# F1C200S.net
KiCad netlist of a schematic drawn in Altium Designer
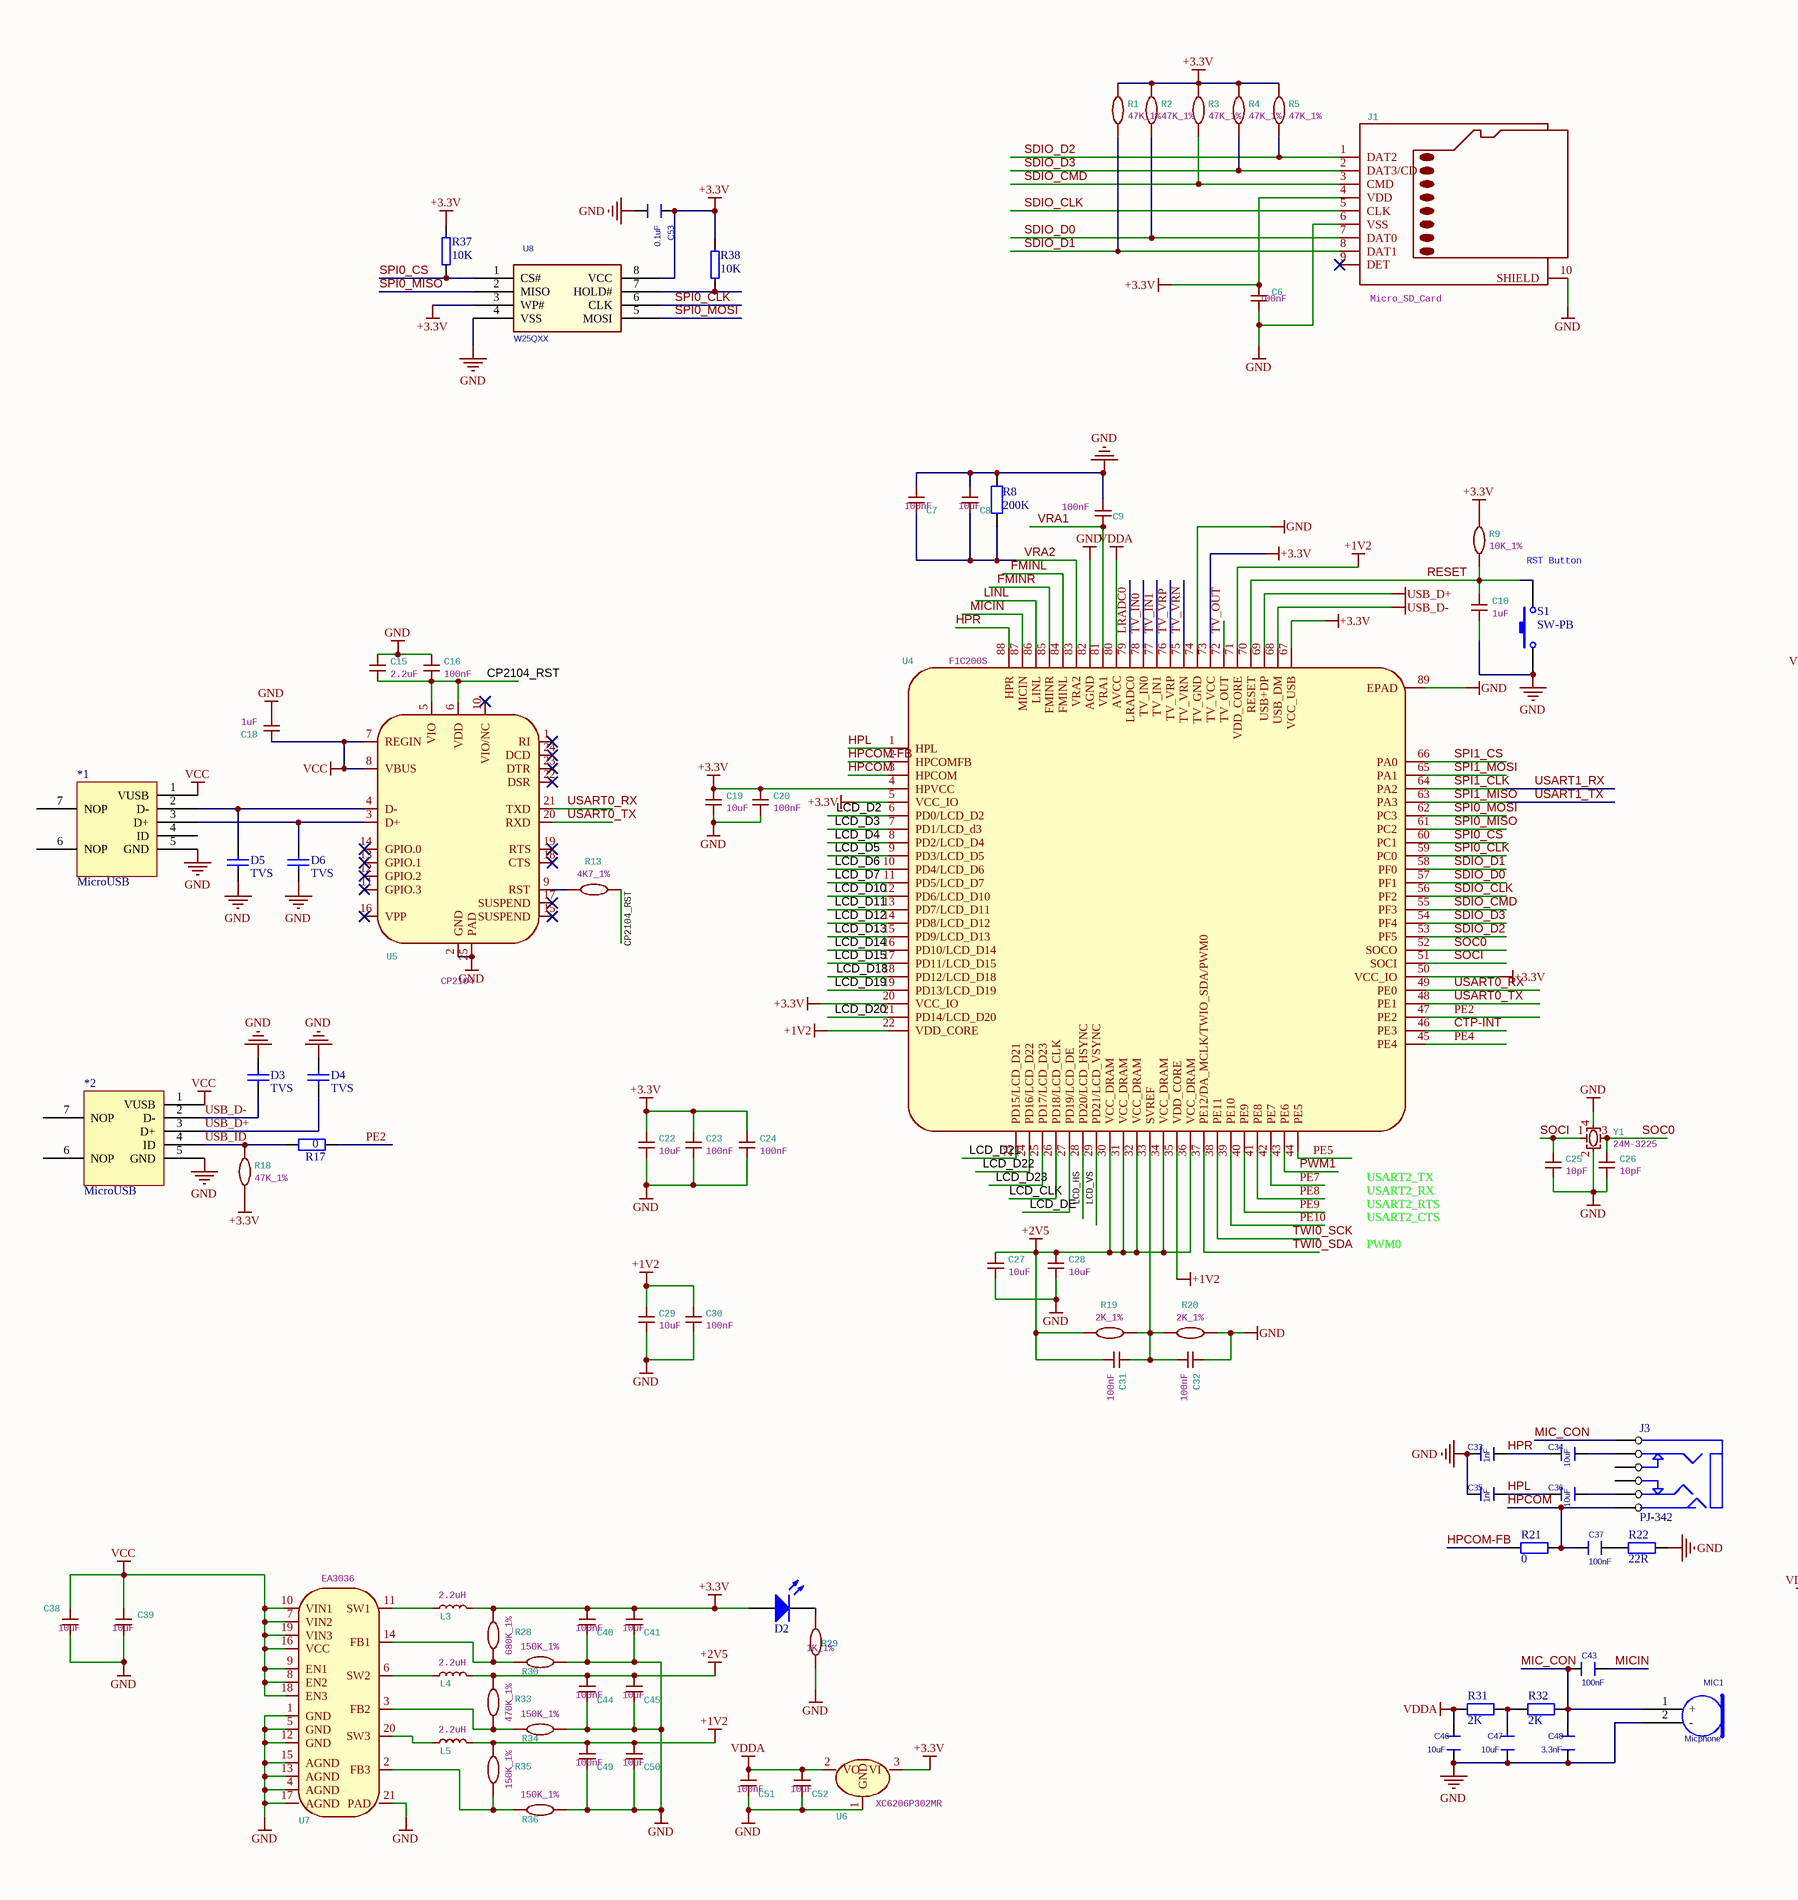
[diagram p0: F1C200S.SchDoc, left]
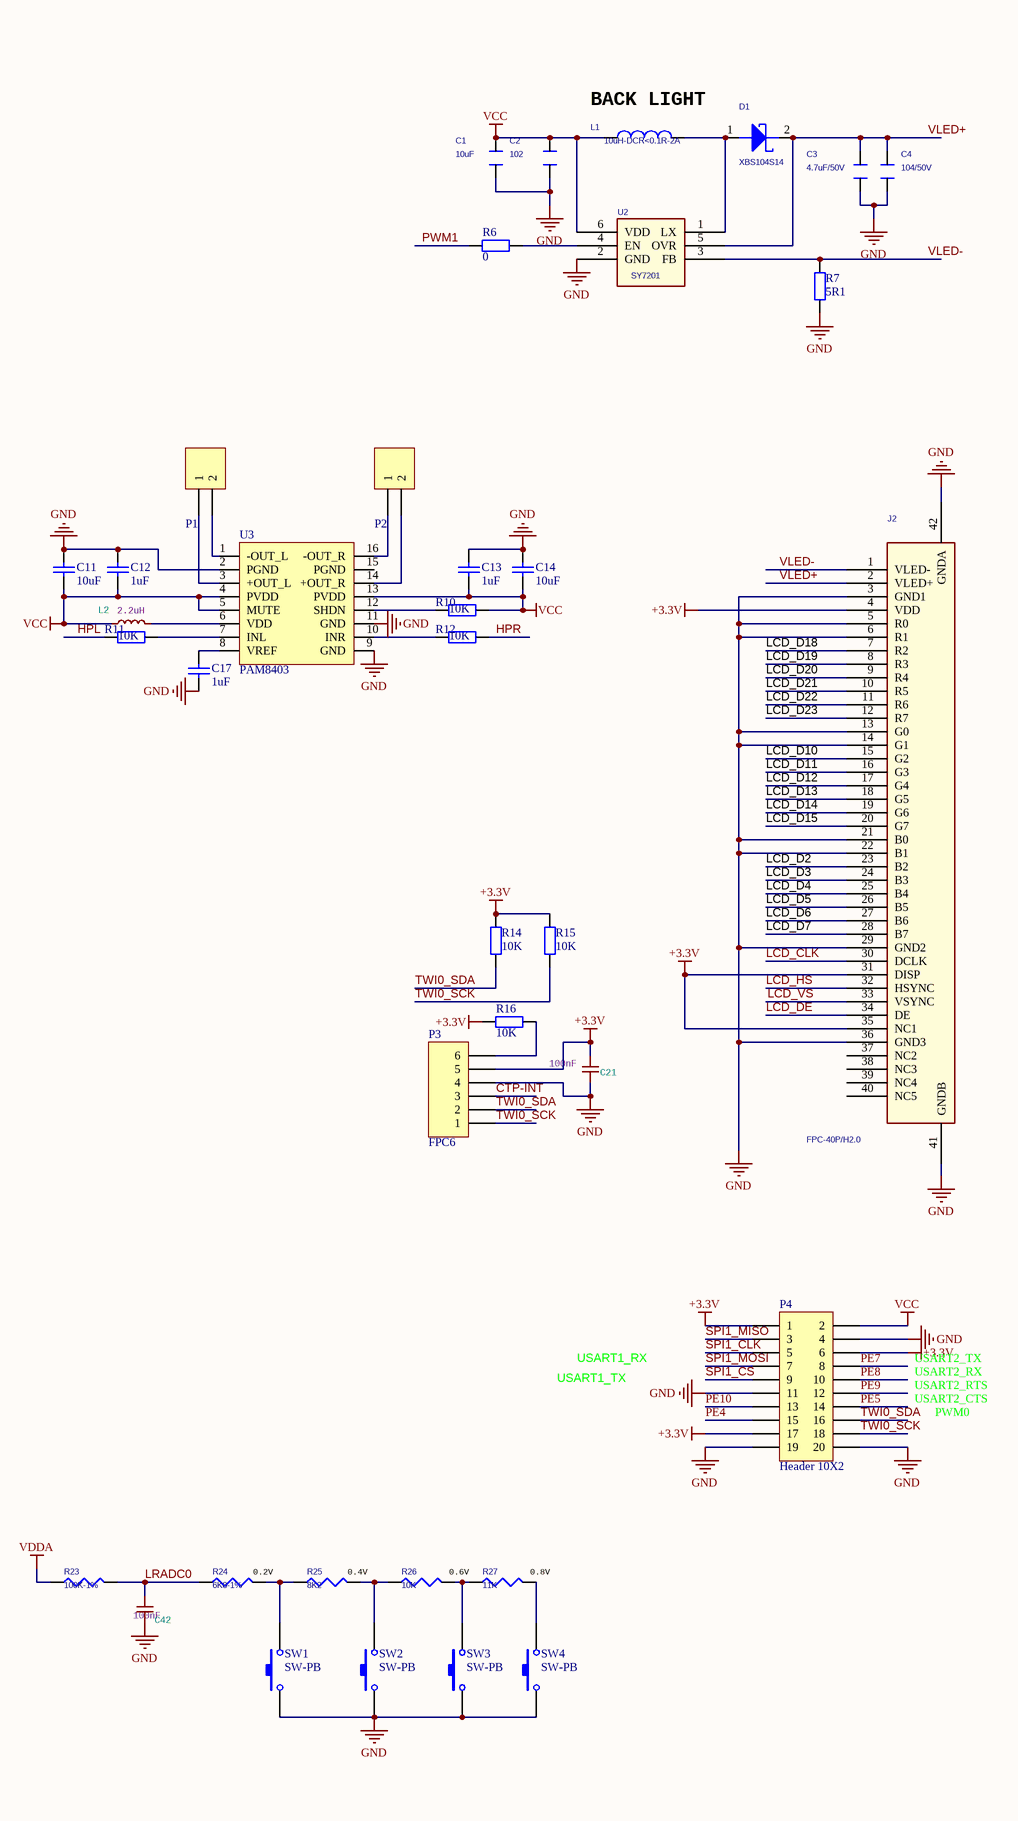
[diagram p1: F1C200S.SchDoc, right]

(export (version "E")
  (design (tool "Eeschema 10.0.6"))
  (components
    (comp (ref "*1")
      (value "MicroUSB")
      (footprint "USB_Micro - 4FP")
      (libsource (lib "USB") (part "MicroUSB"))
    )
    (comp (ref "*2")
      (value "MicroUSB")
      (footprint "USB_Micro - 4FP")
      (libsource (lib "USB") (part "MicroUSB"))
    )
    (comp (ref "C1") (value "10uF") (footprint "C0603") (libsource (lib "*") (part "CAPACITOR_0_Dup5")))
    (comp (ref "C2") (value "102") (footprint "C0603") (libsource (lib "*") (part "CAPACITOR_0_Dup5")))
    (comp (ref "C3") (value "4.7uF/50V") (footprint "C0603") (libsource (lib "*") (part "CAPACITOR_0_Dup5")))
    (comp (ref "C4") (value "104/50V") (footprint "C0603") (libsource (lib "*") (part "CAPACITOR_0_Dup5")))
    (comp (ref "C6")
      (value "03.0009_C0402_100nF")
      (footprint "C0402")
      (libsource (lib "") (part "root_0_03.0009_C0402_100nF__1"))
    )
    (comp (ref "C7")
      (value "03.0009_C0402_100nF")
      (footprint "C0402")
      (libsource (lib "altium-import") (part "root_0_mirrored_03.0009_C0402_100nF_"))
    )
    (comp (ref "C8")
      (value "03.4004_C0603_10uF")
      (footprint "C0603")
      (libsource (lib "altium-import") (part "root_0_mirrored_03.4004_C0603_10uF_"))
    )
    (comp (ref "C9")
      (value "03.0009_C0402_100nF")
      (footprint "C0402")
      (libsource (lib "altium-import") (part "root_3_03.0009_C0402_100nF_"))
    )
    (comp (ref "C10")
      (value "03.0001_C0402_1uF")
      (footprint "C0402")
      (libsource (lib "altium-import") (part "root_0_03.0001_C0402_1uF_"))
    )
    (comp (ref "C11")
      (value "10uF")
      (footprint "C0603")
      (description "无极性电容")
      (fields (field (name "Comment") "Cap") (field (name "PUBLISHER") "Altium Limited"))
      (libsource (lib "fszhang") (part "Cap"))
    )
    (comp (ref "C12")
      (value "1uF")
      (footprint "C0402")
      (description "无极性电容")
      (fields (field (name "Comment") "Cap") (field (name "PUBLISHER") "Altium Limited"))
      (libsource (lib "fszhang") (part "Cap"))
    )
    (comp (ref "C13")
      (value "1uF")
      (footprint "C0402")
      (description "无极性电容")
      (fields (field (name "Comment") "Cap") (field (name "PUBLISHER") "Altium Limited"))
      (libsource (lib "fszhang") (part "Cap"))
    )
    (comp (ref "C14")
      (value "10uF")
      (footprint "C0603")
      (description "无极性电容")
      (fields (field (name "Comment") "Cap") (field (name "PUBLISHER") "Altium Limited"))
      (libsource (lib "fszhang") (part "Cap"))
    )
    (comp (ref "C15")
      (value "03.4002_C0603_2.2uF")
      (footprint "C0402")
      (libsource (lib "altium-import") (part "root_0_03.4002_C0603_2.2uF_"))
    )
    (comp (ref "C16")
      (value "03.0009_C0402_100nF")
      (footprint "C0402")
      (libsource (lib "") (part "root_0_03.0009_C0402_100nF__1"))
    )
    (comp (ref "C17")
      (value "1uF")
      (footprint "C0402")
      (description "无极性电容")
      (fields (field (name "Comment") "Cap") (field (name "PUBLISHER") "Altium Limited"))
      (libsource (lib "fszhang") (part "Cap"))
    )
    (comp (ref "C18")
      (value "03.4001_C0603_1uF")
      (footprint "C0402")
      (libsource (lib "altium-import") (part "root_0_03.4001_C0603_1uF_"))
    )
    (comp (ref "C19")
      (value "03.4004_C0603_10uF")
      (footprint "C0603")
      (libsource (lib "altium-import") (part "root_0_03.4004_C0603_10uF_"))
    )
    (comp (ref "C20")
      (value "03.0009_C0402_100nF")
      (footprint "C0402")
      (libsource (lib "") (part "root_0_03.0009_C0402_100nF__1"))
    )
    (comp (ref "C21")
      (value "03.0009_C0402_100nF")
      (footprint "C0402")
      (libsource (lib "altium-import") (part "root_3_03.0009_C0402_100nF_"))
    )
    (comp (ref "C22")
      (value "03.4004_C0603_10uF")
      (footprint "C0603")
      (libsource (lib "altium-import") (part "root_0_03.4004_C0603_10uF_"))
    )
    (comp (ref "C23")
      (value "03.0009_C0402_100nF")
      (footprint "C0402")
      (libsource (lib "") (part "root_0_03.0009_C0402_100nF__1"))
    )
    (comp (ref "C24")
      (value "03.0009_C0402_100nF")
      (footprint "C0402")
      (libsource (lib "") (part "root_0_03.0009_C0402_100nF__1"))
    )
    (comp (ref "C25")
      (value "03.0003_C0402_10pF")
      (footprint "C0402")
      (libsource (lib "altium-import") (part "root_0_03.0003_C0402_10pF_"))
    )
    (comp (ref "C26")
      (value "03.0003_C0402_10pF")
      (footprint "C0402")
      (libsource (lib "altium-import") (part "root_0_03.0003_C0402_10pF_"))
    )
    (comp (ref "C27")
      (value "03.4004_C0603_10uF")
      (footprint "C0603")
      (libsource (lib "altium-import") (part "root_0_03.4004_C0603_10uF_"))
    )
    (comp (ref "C28")
      (value "03.4004_C0603_10uF")
      (footprint "C0603")
      (libsource (lib "altium-import") (part "root_0_03.4004_C0603_10uF_"))
    )
    (comp (ref "C29")
      (value "03.4004_C0603_10uF")
      (footprint "C0603")
      (libsource (lib "altium-import") (part "root_0_03.4004_C0603_10uF_"))
    )
    (comp (ref "C30")
      (value "03.0009_C0402_100nF")
      (footprint "C0402")
      (libsource (lib "") (part "root_0_03.0009_C0402_100nF__1"))
    )
    (comp (ref "C31")
      (value "03.0009_C0402_100nF")
      (footprint "C0402")
      (libsource (lib "altium-import") (part "root_0_03.0009_C0402_100nF_"))
    )
    (comp (ref "C32")
      (value "03.0009_C0402_100nF")
      (footprint "C0402")
      (libsource (lib "altium-import") (part "root_0_03.0009_C0402_100nF_"))
    )
    (comp (ref "C33") (value "1nF") (footprint "C0402") (libsource (lib "*") (part "CAPACITOR_Dup3")))
    (comp (ref "C34") (value "10uF") (footprint "C0603") (libsource (lib "*") (part "CAPACITOR_Dup3")))
    (comp (ref "C35") (value "1nF") (footprint "C0402") (libsource (lib "*") (part "CAPACITOR_Dup3")))
    (comp (ref "C36") (value "10uF") (footprint "C0603") (libsource (lib "*") (part "CAPACITOR_Dup3")))
    (comp (ref "C37") (value "100nF") (footprint "C0402") (libsource (lib "*") (part "CAPACITOR_Dup3")))
    (comp (ref "C38")
      (value "03.4004_C0603_10uF")
      (footprint "C0603")
      (libsource (lib "altium-import") (part "root_0_mirrored_03.4004_C0603_10uF_"))
    )
    (comp (ref "C39")
      (value "03.4004_C0603_10uF")
      (footprint "C0603")
      (libsource (lib "altium-import") (part "root_0_mirrored_03.4004_C0603_10uF_"))
    )
    (comp (ref "C40")
      (value "03.0009_C0402_100nF")
      (footprint "C0402")
      (libsource (lib "altium-import") (part "root_0_mirrored_03.0009_C0402_100nF_"))
    )
    (comp (ref "C41")
      (value "03.4004_C0603_10uF")
      (footprint "C0603")
      (libsource (lib "altium-import") (part "root_0_mirrored_03.4004_C0603_10uF_"))
    )
    (comp (ref "C42")
      (value "03.0009_C0402_100nF")
      (footprint "C0402")
      (libsource (lib "altium-import") (part "root_0_mirrored_03.0009_C0402_100nF_"))
    )
    (comp (ref "C43") (value "100nF") (footprint "C0402") (libsource (lib "*") (part "CAPACITOR_Dup3")))
    (comp (ref "C44")
      (value "03.0009_C0402_100nF")
      (footprint "C0402")
      (libsource (lib "altium-import") (part "root_0_mirrored_03.0009_C0402_100nF_"))
    )
    (comp (ref "C45")
      (value "03.4004_C0603_10uF")
      (footprint "C0603")
      (libsource (lib "altium-import") (part "root_0_mirrored_03.4004_C0603_10uF_"))
    )
    (comp (ref "C46") (value "10uF") (footprint "C0603") (libsource (lib "*") (part "CAPACITOR_Dup3")))
    (comp (ref "C47") (value "10uF") (footprint "C0603") (libsource (lib "*") (part "CAPACITOR_Dup3")))
    (comp (ref "C48") (value "3.3nF") (footprint "C0402") (libsource (lib "*") (part "CAPACITOR_Dup3")))
    (comp (ref "C49")
      (value "03.0009_C0402_100nF")
      (footprint "C0402")
      (libsource (lib "altium-import") (part "root_0_mirrored_03.0009_C0402_100nF_"))
    )
    (comp (ref "C50")
      (value "03.4004_C0603_10uF")
      (footprint "C0603")
      (libsource (lib "altium-import") (part "root_0_mirrored_03.4004_C0603_10uF_"))
    )
    (comp (ref "C51")
      (value "03.0009_C0402_100nF")
      (footprint "C0402")
      (libsource (lib "altium-import") (part "root_0_mirrored_03.0009_C0402_100nF_"))
    )
    (comp (ref "C52")
      (value "03.4004_C0603_10uF")
      (footprint "C0603")
      (libsource (lib "altium-import") (part "root_0_mirrored_03.4004_C0603_10uF_"))
    )
    (comp (ref "C53") (value "0.1uF") (footprint "C0402") (libsource (lib "*") (part "CAPACITOR_Dup1")))
    (comp (ref "D1")
      (value "XBS104S14")
      (footprint "SOD123")
      (description "RoHS 1.0 Ampere Schottky Barrier Rectifiers  SOD-123")
      (libsource (lib "*") (part "DIODE SCHOTTKY_0"))
    )
    (comp (ref "D2")
      (value "LED0")
      (footprint "0603LED")
      (description "发光二极管")
      (fields (field (name "PUBLISHER") "Altium Limited"))
      (libsource (lib "fszhang") (part "LED0"))
    )
    (comp (ref "D3")
      (value "TVS")
      (footprint "C0402")
      (description "无极性电容")
      (fields (field (name "Comment") "Cap") (field (name "PUBLISHER") "Altium Limited"))
      (libsource (lib "fszhang") (part "Cap"))
    )
    (comp (ref "D4")
      (value "TVS")
      (footprint "C0402")
      (description "无极性电容")
      (fields (field (name "Comment") "Cap") (field (name "PUBLISHER") "Altium Limited"))
      (libsource (lib "fszhang") (part "Cap"))
    )
    (comp (ref "D5")
      (value "TVS")
      (footprint "C0402")
      (description "无极性电容")
      (fields (field (name "Comment") "Cap") (field (name "PUBLISHER") "Altium Limited"))
      (libsource (lib "fszhang") (part "Cap"))
    )
    (comp (ref "D6")
      (value "TVS")
      (footprint "C0402")
      (description "无极性电容")
      (fields (field (name "Comment") "Cap") (field (name "PUBLISHER") "Altium Limited"))
      (libsource (lib "fszhang") (part "Cap"))
    )
    (comp (ref "J1")
      (value "10.0001_Micro_SD_Card")
      (footprint "SDCARD-M")
      (libsource (lib "altium-import") (part "root_0_10.0001_Micro_SD_Card_"))
    )
    (comp (ref "J2")
      (value "FPC-40P/H2.0")
      (footprint "FPC0.5-40P-B")
      (libsource (lib "*") (part "LCD-LW500AC9001_0"))
    )
    (comp (ref "J3") (value "PJ-342") (footprint "PJ-342") (libsource (lib "lpi-nano-dock") (part "PJ-342")))
    (comp (ref "L1")
      (value "10uH-DCR<0.1R-2A")
      (footprint "3015")
      (description "RoHS Power Inductor 22uH 300mA H<1.8MM,CD32")
      (libsource (lib "*") (part "INDUCTOR_3"))
    )
    (comp (ref "L2")
      (value "06.0102_L2520_2.2uH")
      (footprint "3015")
      (libsource (lib "altium-import") (part "root_0_mirrored_06.0102_L2520_2.2uH_"))
    )
    (comp (ref "L3")
      (value "06.0102_L2520_2.2uH")
      (footprint "3015")
      (libsource (lib "altium-import") (part "root_0_mirrored_06.0102_L2520_2.2uH_"))
    )
    (comp (ref "L4")
      (value "06.0102_L2520_2.2uH")
      (footprint "3015")
      (libsource (lib "altium-import") (part "root_0_mirrored_06.0102_L2520_2.2uH_"))
    )
    (comp (ref "L5")
      (value "06.0102_L2520_2.2uH")
      (footprint "3015")
      (libsource (lib "altium-import") (part "root_0_mirrored_06.0102_L2520_2.2uH_"))
    )
    (comp (ref "MIC1") (value "Micphone") (footprint "MIC_6022") (libsource (lib "*") (part "Micphone_0")))
    (comp (ref "P1")
      (value "Header 2")
      (footprint "HDR2X1_A")
      (description "接插件")
      (fields (field (name "PUBLISHER") "Altium Limited"))
      (libsource (lib "fszhang") (part "Header 2"))
    )
    (comp (ref "P2")
      (value "Header 2")
      (footprint "HDR2X1_A")
      (description "接插件")
      (fields (field (name "PUBLISHER") "Altium Limited"))
      (libsource (lib "fszhang") (part "Header 2"))
    )
    (comp (ref "P3")
      (value "FPC6")
      (footprint "FPC0.5-6P-A")
      (description "接插件")
      (fields (field (name "PUBLISHER") "Altium Limited"))
      (libsource (lib "fszhang") (part "Header 6"))
    )
    (comp (ref "P4")
      (value "Header 10X2")
      (footprint "HDR2X10")
      (description "Header, 10-Pin, Dual row")
      (fields (field (name "PUBLISHER") "Altium Limited"))
      (libsource (lib "Miscellaneous Connectors") (part "Header 10X2"))
    )
    (comp (ref "R1")
      (value "02.0014_R0402_10K_1%")
      (footprint "R0402")
      (libsource (lib "altium-import") (part "root_0_02.0014_R0402_47K_1%_"))
    )
    (comp (ref "R2")
      (value "02.0014_R0402_10K_1%")
      (footprint "R0402")
      (libsource (lib "altium-import") (part "root_0_02.0014_R0402_47K_1%_"))
    )
    (comp (ref "R3")
      (value "02.0014_R0402_10K_1%")
      (footprint "R0402")
      (libsource (lib "altium-import") (part "root_0_02.0014_R0402_47K_1%_"))
    )
    (comp (ref "R4")
      (value "02.0014_R0402_10K_1%")
      (footprint "R0402")
      (libsource (lib "altium-import") (part "root_0_02.0014_R0402_47K_1%_"))
    )
    (comp (ref "R5")
      (value "02.0014_R0402_10K_1%")
      (footprint "R0402")
      (libsource (lib "altium-import") (part "root_0_02.0014_R0402_47K_1%_"))
    )
    (comp (ref "R6")
      (value "0")
      (footprint "R0402")
      (description "贴片电阻")
      (fields (field (name "Comment") "Res1") (field (name "PUBLISHER") "Altium Limited"))
      (libsource (lib "") (part "Res1_1"))
    )
    (comp (ref "R7")
      (value "5R1")
      (footprint "R0603")
      (description "贴片电阻")
      (fields (field (name "Comment") "Res1") (field (name "PUBLISHER") "Altium Limited"))
      (libsource (lib "fszhang") (part "Res1"))
    )
    (comp (ref "R8")
      (value "200K")
      (footprint "R0402")
      (description "贴片电阻")
      (fields (field (name "Comment") "Res1") (field (name "PUBLISHER") "Altium Limited"))
      (libsource (lib "") (part "Res1_2"))
    )
    (comp (ref "R9")
      (value "02.0008_R0402_10K_1%")
      (footprint "R0402")
      (libsource (lib "altium-import") (part "root_0_02.0008_R0402_10K_1%_"))
    )
    (comp (ref "R10")
      (value "10K")
      (footprint "R0402")
      (description "贴片电阻")
      (fields (field (name "Comment") "Res1") (field (name "PUBLISHER") "Altium Limited"))
      (libsource (lib "") (part "Res1_2"))
    )
    (comp (ref "R11")
      (value "10K")
      (footprint "R0402")
      (description "贴片电阻")
      (fields (field (name "Comment") "Res1") (field (name "PUBLISHER") "Altium Limited"))
      (libsource (lib "") (part "Res1_3"))
    )
    (comp (ref "R12")
      (value "10K")
      (footprint "R0402")
      (description "贴片电阻")
      (fields (field (name "Comment") "Res1") (field (name "PUBLISHER") "Altium Limited"))
      (libsource (lib "") (part "Res1_2"))
    )
    (comp (ref "R13")
      (value "02.0005_R0402_4K7_1%")
      (footprint "R0402")
      (libsource (lib "altium-import") (part "root_0_02.0005_R0402_4K7_1%_"))
    )
    (comp (ref "R14")
      (value "10K")
      (footprint "R0402")
      (description "贴片电阻")
      (fields (field (name "Comment") "Res1") (field (name "PUBLISHER") "Altium Limited"))
      (libsource (lib "") (part "Res1_1"))
    )
    (comp (ref "R15")
      (value "10K")
      (footprint "R0402")
      (description "贴片电阻")
      (fields (field (name "Comment") "Res1") (field (name "PUBLISHER") "Altium Limited"))
      (libsource (lib "") (part "Res1_1"))
    )
    (comp (ref "R16")
      (value "10K")
      (footprint "R0402")
      (description "贴片电阻")
      (fields (field (name "Comment") "Res1") (field (name "PUBLISHER") "Altium Limited"))
      (libsource (lib "fszhang") (part "Res1"))
    )
    (comp (ref "R17")
      (value "0")
      (footprint "R0402")
      (description "贴片电阻")
      (fields (field (name "Comment") "Res1") (field (name "PUBLISHER") "Altium Limited"))
      (libsource (lib "") (part "Res1_1"))
    )
    (comp (ref "R18")
      (value "02.0014_R0402_10K_1%")
      (footprint "R0402")
      (libsource (lib "altium-import") (part "root_0_02.0014_R0402_47K_1%_"))
    )
    (comp (ref "R19")
      (value "02.0026_R0402_2K_1%")
      (footprint "R0402")
      (libsource (lib "altium-import") (part "root_0_02.0026_R0402_2K_1%_"))
    )
    (comp (ref "R20")
      (value "02.0026_R0402_2K_1%")
      (footprint "R0402")
      (libsource (lib "altium-import") (part "root_0_02.0026_R0402_2K_1%_"))
    )
    (comp (ref "R21")
      (value "0")
      (footprint "R0402")
      (description "贴片电阻")
      (fields (field (name "Comment") "Res1") (field (name "PUBLISHER") "Altium Limited"))
      (libsource (lib "") (part "Res1_3"))
    )
    (comp (ref "R22")
      (value "22R")
      (footprint "R0603")
      (description "贴片电阻")
      (fields (field (name "Comment") "Res1") (field (name "PUBLISHER") "Altium Limited"))
      (libsource (lib "") (part "Res1_3"))
    )
    (comp (ref "R23") (value "100K-1%") (footprint "R0402") (libsource (lib "*") (part "R1 0805_Dup1")))
    (comp (ref "R24") (value "6K8-1%") (footprint "R0402") (libsource (lib "*") (part "R1 0805_Dup1")))
    (comp (ref "R25") (value "8K2") (footprint "R0402") (libsource (lib "*") (part "R1 0805_Dup1")))
    (comp (ref "R26") (value "10K") (footprint "R0402") (libsource (lib "*") (part "R1 0805_Dup1")))
    (comp (ref "R27") (value "11K") (footprint "R0402") (libsource (lib "*") (part "R1 0805_Dup1")))
    (comp (ref "R28")
      (value "02.0025_R0402_680K_1%")
      (footprint "R0402")
      (libsource (lib "altium-import") (part "root_0_mirrored_02.0025_R0402_680K_1%_"))
    )
    (comp (ref "R29")
      (value "02.0003_R0402_1K_1%")
      (footprint "R0402")
      (libsource (lib "altium-import") (part "root_0_mirrored_02.0003_R0402_1K_1%_"))
    )
    (comp (ref "R30")
      (value "02.0023_R0402_150K_1%")
      (footprint "R0402")
      (libsource (lib "altium-import") (part "root_0_mirrored_02.0023_R0402_150K_1%_"))
    )
    (comp (ref "R31")
      (value "2K")
      (footprint "R0402")
      (description "贴片电阻")
      (fields (field (name "Comment") "Res1") (field (name "PUBLISHER") "Altium Limited"))
      (libsource (lib "") (part "Res1_3"))
    )
    (comp (ref "R32")
      (value "2K")
      (footprint "R0402")
      (description "贴片电阻")
      (fields (field (name "Comment") "Res1") (field (name "PUBLISHER") "Altium Limited"))
      (libsource (lib "") (part "Res1_3"))
    )
    (comp (ref "R33")
      (value "02.0024_R0402_470K_1%")
      (footprint "R0402")
      (libsource (lib "altium-import") (part "root_0_mirrored_02.0024_R0402_470K_1%_"))
    )
    (comp (ref "R34")
      (value "02.0023_R0402_150K_1%")
      (footprint "R0402")
      (libsource (lib "altium-import") (part "root_0_mirrored_02.0023_R0402_150K_1%_"))
    )
    (comp (ref "R35")
      (value "02.0023_R0402_150K_1%")
      (footprint "R0402")
      (libsource (lib "") (part "root_0_mirrored_02.0023_R0402_150K_1%__1"))
    )
    (comp (ref "R36")
      (value "02.0023_R0402_150K_1%")
      (footprint "R0402")
      (libsource (lib "altium-import") (part "root_0_mirrored_02.0023_R0402_150K_1%_"))
    )
    (comp (ref "R37")
      (value "10K")
      (footprint "R0402")
      (description "Resistor")
      (libsource (lib "Renhaibo") (part "电阻Ω"))
    )
    (comp (ref "R38")
      (value "10K")
      (footprint "R0402")
      (description "Resistor")
      (libsource (lib "Renhaibo") (part "电阻Ω"))
    )
    (comp (ref "S1")
      (value "SW-PB")
      (footprint "SW_PB4_3*4*2.5")
      (description "微动开关")
      (fields (field (name "PUBLISHER") "Altium Limited"))
      (libsource (lib "fszhang") (part "SW-PB"))
    )
    (comp (ref "SW1")
      (value "SW-PB")
      (footprint "SW_PB4_3*4*2.5")
      (description "微动开关")
      (fields (field (name "PUBLISHER") "Altium Limited"))
      (libsource (lib "fszhang") (part "SW-PB"))
    )
    (comp (ref "SW2")
      (value "SW-PB")
      (footprint "SW_PB4_3*4*2.5")
      (description "微动开关")
      (fields (field (name "PUBLISHER") "Altium Limited"))
      (libsource (lib "fszhang") (part "SW-PB"))
    )
    (comp (ref "SW3")
      (value "SW-PB")
      (footprint "SW_PB4_3*4*2.5")
      (description "微动开关")
      (fields (field (name "PUBLISHER") "Altium Limited"))
      (libsource (lib "fszhang") (part "SW-PB"))
    )
    (comp (ref "SW4")
      (value "SW-PB")
      (footprint "SW_PB4_3*4*2.5")
      (description "微动开关")
      (fields (field (name "PUBLISHER") "Altium Limited"))
      (libsource (lib "fszhang") (part "SW-PB"))
    )
    (comp (ref "U2") (value "SY7201") (footprint "SOT-23-6") (libsource (lib "*") (part "AP3031")))
    (comp (ref "U3") (value "PAM8403") (footprint "SOP-16") (libsource (lib "STM32 SCH") (part "PAM8403")))
    (comp (ref "U4")
      (value "08.0001_F1C200S")
      (footprint "QFN-88_EP_10X10_PITCH0.4MM")
      (libsource (lib "altium-import") (part "root_0_08.0001_F1C200S_"))
    )
    (comp (ref "U5")
      (value "09.0001_CP2104")
      (footprint "QFN-24-1EP_4X4MM_P0.5MM_EP2.6X2.6MM")
      (libsource (lib "altium-import") (part "root_0_09.0001_CP2104_"))
    )
    (comp (ref "U6")
      (value "09.0103_XC6206")
      (footprint "SOT-23")
      (libsource (lib "altium-import") (part "root_0_mirrored_09.0103_XC6206_"))
    )
    (comp (ref "U7")
      (value "09.0102_EA3036")
      (footprint "QFN-20_EP_3X3_PITCH0.4MM")
      (libsource (lib "altium-import") (part "root_0_mirrored_09.0102_EA3036_"))
    )
    (comp (ref "U8") (value "W25QXX") (footprint "SOP-8M(PAD)") (libsource (lib "*") (part "SPI-NOR-SO8")))
    (comp (ref "Y1")
      (value "07.0403_Crystal_24M_3225")
      (footprint "CRYSTAL-2.5X2.0")
      (libsource (lib "altium-import") (part "root_0_07.0403_Crystal_24M_3225_"))
    )
  )
  (nets
    (net (code "1") (name "+1V2") (class "Default")
      (node (ref "C29") (pin "1") (pintype "passive"))
      (node (ref "C30") (pin "1") (pintype "passive"))
      (node (ref "C49") (pin "1") (pintype "passive"))
      (node (ref "C50") (pin "1") (pintype "passive"))
      (node (ref "L5") (pin "1") (pinfunction "1_1") (pintype "passive"))
      (node (ref "R35") (pin "2") (pinfunction "2_2") (pintype "passive"))
      (node (ref "U4") (pin "22") (pinfunction "VDD_CORE_22") (pintype "passive"))
      (node (ref "U4") (pin "35") (pinfunction "VDD_CORE_35") (pintype "passive"))
      (node (ref "U4") (pin "71") (pinfunction "VDD_CORE_71") (pintype "passive"))
    )
    (net (code "2") (name "+2V5") (class "Default")
      (node (ref "C27") (pin "1") (pintype "passive"))
      (node (ref "C28") (pin "1") (pintype "passive"))
      (node (ref "C31") (pin "2") (pintype "passive"))
      (node (ref "C44") (pin "1") (pintype "passive"))
      (node (ref "C45") (pin "1") (pintype "passive"))
      (node (ref "L4") (pin "1") (pinfunction "1_1") (pintype "passive"))
      (node (ref "R19") (pin "2") (pinfunction "2_2") (pintype "passive"))
      (node (ref "R33") (pin "2") (pinfunction "2_2") (pintype "passive"))
      (node (ref "U4") (pin "30") (pinfunction "VCC_DRAM_30") (pintype "passive"))
      (node (ref "U4") (pin "31") (pinfunction "VCC_DRAM_31") (pintype "passive"))
      (node (ref "U4") (pin "32") (pinfunction "VCC_DRAM_32") (pintype "passive"))
      (node (ref "U4") (pin "34") (pinfunction "VCC_DRAM_34") (pintype "passive"))
      (node (ref "U4") (pin "36") (pinfunction "VCC_DRAM_36") (pintype "passive"))
    )
    (net (code "3") (name "+3.3V") (class "Default")
      (node (ref "C19") (pin "1") (pintype "passive"))
      (node (ref "C20") (pin "1") (pintype "passive"))
      (node (ref "C21") (pin "2") (pintype "passive"))
      (node (ref "C22") (pin "1") (pintype "passive"))
      (node (ref "C23") (pin "1") (pintype "passive"))
      (node (ref "C24") (pin "1") (pintype "passive"))
      (node (ref "C40") (pin "1") (pintype "passive"))
      (node (ref "C41") (pin "1") (pintype "passive"))
      (node (ref "C53") (pin "2") (pinfunction "2_2") (pintype "passive"))
      (node (ref "C6") (pin "1") (pintype "passive"))
      (node (ref "D2") (pin "1") (pinfunction "A_1") (pintype "passive"))
      (node (ref "J1") (pin "4") (pinfunction "VDD_4") (pintype "passive"))
      (node (ref "J2") (pin "31") (pinfunction "DISP_31") (pintype "passive"))
      (node (ref "J2") (pin "35") (pinfunction "NC1_35") (pintype "passive"))
      (node (ref "J2") (pin "4") (pinfunction "VDD_4") (pintype "passive"))
      (node (ref "L3") (pin "1") (pinfunction "1_1") (pintype "passive"))
      (node (ref "P3") (pin "5") (pinfunction "5_5") (pintype "passive"))
      (node (ref "P4") (pin "1") (pinfunction "1_1") (pintype "passive"))
      (node (ref "P4") (pin "17") (pinfunction "17_17") (pintype "passive"))
      (node (ref "P4") (pin "6") (pinfunction "6_6") (pintype "passive"))
      (node (ref "R1") (pin "1") (pinfunction "1_1") (pintype "passive"))
      (node (ref "R14") (pin "2") (pinfunction "2_2") (pintype "passive"))
      (node (ref "R15") (pin "2") (pinfunction "2_2") (pintype "passive"))
      (node (ref "R16") (pin "2") (pinfunction "2_2") (pintype "passive"))
      (node (ref "R18") (pin "2") (pinfunction "2_2") (pintype "passive"))
      (node (ref "R2") (pin "1") (pinfunction "1_1") (pintype "passive"))
      (node (ref "R28") (pin "2") (pinfunction "2_2") (pintype "passive"))
      (node (ref "R3") (pin "1") (pinfunction "1_1") (pintype "passive"))
      (node (ref "R37") (pin "1") (pinfunction "1_1") (pintype "passive"))
      (node (ref "R38") (pin "1") (pinfunction "1_1") (pintype "passive"))
      (node (ref "R4") (pin "1") (pinfunction "1_1") (pintype "passive"))
      (node (ref "R5") (pin "1") (pinfunction "1_1") (pintype "passive"))
      (node (ref "R9") (pin "1") (pinfunction "1_1") (pintype "passive"))
      (node (ref "U4") (pin "20") (pinfunction "VCC_IO_20") (pintype "passive"))
      (node (ref "U4") (pin "4") (pinfunction "HPVCC_4") (pintype "passive"))
      (node (ref "U4") (pin "5") (pinfunction "VCC_IO_5") (pintype "passive"))
      (node (ref "U4") (pin "50") (pinfunction "VCC_IO_50") (pintype "passive"))
      (node (ref "U4") (pin "67") (pinfunction "VCC_USB_67") (pintype "passive"))
      (node (ref "U4") (pin "73") (pinfunction "TV_VCC_73") (pintype "passive"))
      (node (ref "U6") (pin "3") (pinfunction "VI_3") (pintype "passive"))
      (node (ref "U8") (pin "3") (pinfunction "WP#_3") (pintype "passive"))
      (node (ref "U8") (pin "8") (pinfunction "VCC_8") (pintype "passive"))
    )
    (net (code "4") (name "/CP2104_RST") (class "Default")
      (node (ref "C15") (pin "2") (pintype "passive"))
      (node (ref "C16") (pin "2") (pintype "passive"))
      (node (ref "R13") (pin "2") (pinfunction "2_2") (pintype "passive"))
      (node (ref "U5") (pin "5") (pinfunction "VIO_5") (pintype "passive"))
      (node (ref "U5") (pin "6") (pinfunction "VDD_6") (pintype "passive"))
    )
    (net (code "5") (name "/CTP-INT") (class "Default")
      (node (ref "P3") (pin "3") (pinfunction "3_3") (pintype "passive"))
      (node (ref "U4") (pin "46") (pinfunction "PE3_46") (pintype "passive"))
    )
    (net (code "6") (name "/FMINL") (class "Default")
      (node (ref "U4") (pin "84") (pinfunction "FMINL_84") (pintype "passive"))
    )
    (net (code "7") (name "/FMINR") (class "Default")
      (node (ref "U4") (pin "85") (pinfunction "FMINR_85") (pintype "passive"))
    )
    (net (code "8") (name "/HPCOM") (class "Default")
      (node (ref "C37") (pin "2") (pinfunction "2_2") (pintype "passive"))
      (node (ref "J3") (pin "3") (pinfunction "GND_3") (pintype "passive"))
      (node (ref "R21") (pin "1") (pinfunction "1_1") (pintype "passive"))
      (node (ref "U4") (pin "3") (pinfunction "HPCOM_3") (pintype "passive"))
    )
    (net (code "9") (name "/HPCOM-FB") (class "Default")
      (node (ref "R21") (pin "2") (pinfunction "2_2") (pintype "passive"))
      (node (ref "U4") (pin "2") (pinfunction "HPCOMFB_2") (pintype "passive"))
    )
    (net (code "10") (name "/HPL") (class "Default")
      (node (ref "C35") (pin "2") (pinfunction "2_2") (pintype "passive"))
      (node (ref "C36") (pin "1") (pinfunction "1_1") (pintype "passive"))
      (node (ref "R11") (pin "2") (pinfunction "2_2") (pintype "passive"))
      (node (ref "U4") (pin "1") (pinfunction "HPL_1") (pintype "passive"))
    )
    (net (code "11") (name "/HPR") (class "Default")
      (node (ref "C33") (pin "2") (pinfunction "2_2") (pintype "passive"))
      (node (ref "C34") (pin "1") (pinfunction "1_1") (pintype "passive"))
      (node (ref "R12") (pin "2") (pinfunction "2_2") (pintype "passive"))
      (node (ref "U4") (pin "88") (pinfunction "HPR_88") (pintype "passive"))
    )
    (net (code "12") (name "/LCD_CLK") (class "Default")
      (node (ref "J2") (pin "30") (pinfunction "DCLK_30") (pintype "passive"))
      (node (ref "U4") (pin "26") (pinfunction "PD18/LCD_CLK_26") (pintype "passive"))
    )
    (net (code "13") (name "/LCD_D2") (class "Default")
      (node (ref "J2") (pin "23") (pinfunction "B2_23") (pintype "passive"))
      (node (ref "U4") (pin "6") (pinfunction "PD0/LCD_D2_6") (pintype "passive"))
    )
    (net (code "14") (name "/LCD_D3") (class "Default")
      (node (ref "J2") (pin "24") (pinfunction "B3_24") (pintype "passive"))
      (node (ref "U4") (pin "7") (pinfunction "PD1/LCD_d3_7") (pintype "passive"))
    )
    (net (code "15") (name "/LCD_D4") (class "Default")
      (node (ref "J2") (pin "25") (pinfunction "B4_25") (pintype "passive"))
      (node (ref "U4") (pin "8") (pinfunction "PD2/LCD_D4_8") (pintype "passive"))
    )
    (net (code "16") (name "/LCD_D5") (class "Default")
      (node (ref "J2") (pin "26") (pinfunction "B5_26") (pintype "passive"))
      (node (ref "U4") (pin "9") (pinfunction "PD3/LCD_D5_9") (pintype "passive"))
    )
    (net (code "17") (name "/LCD_D6") (class "Default")
      (node (ref "J2") (pin "27") (pinfunction "B6_27") (pintype "passive"))
      (node (ref "U4") (pin "10") (pinfunction "PD4/LCD_D6_10") (pintype "passive"))
    )
    (net (code "18") (name "/LCD_D7") (class "Default")
      (node (ref "J2") (pin "28") (pinfunction "B7_28") (pintype "passive"))
      (node (ref "U4") (pin "11") (pinfunction "PD5/LCD_D7_11") (pintype "passive"))
    )
    (net (code "19") (name "/LCD_D10") (class "Default")
      (node (ref "J2") (pin "15") (pinfunction "G2_15") (pintype "passive"))
      (node (ref "U4") (pin "12") (pinfunction "PD6/LCD_D10_12") (pintype "passive"))
    )
    (net (code "20") (name "/LCD_D11") (class "Default")
      (node (ref "J2") (pin "16") (pinfunction "G3_16") (pintype "passive"))
      (node (ref "U4") (pin "13") (pinfunction "PD7/LCD_D11_13") (pintype "passive"))
    )
    (net (code "21") (name "/LCD_D12") (class "Default")
      (node (ref "J2") (pin "17") (pinfunction "G4_17") (pintype "passive"))
      (node (ref "U4") (pin "14") (pinfunction "PD8/LCD_D12_14") (pintype "passive"))
    )
    (net (code "22") (name "/LCD_D13") (class "Default")
      (node (ref "J2") (pin "18") (pinfunction "G5_18") (pintype "passive"))
      (node (ref "U4") (pin "15") (pinfunction "PD9/LCD_D13_15") (pintype "passive"))
    )
    (net (code "23") (name "/LCD_D14") (class "Default")
      (node (ref "J2") (pin "19") (pinfunction "G6_19") (pintype "passive"))
      (node (ref "U4") (pin "16") (pinfunction "PD10/LCD_D14_16") (pintype "passive"))
    )
    (net (code "24") (name "/LCD_D15") (class "Default")
      (node (ref "J2") (pin "20") (pinfunction "G7_20") (pintype "passive"))
      (node (ref "U4") (pin "17") (pinfunction "PD11/LCD_D15_17") (pintype "passive"))
    )
    (net (code "25") (name "/LCD_D18") (class "Default")
      (node (ref "J2") (pin "7") (pinfunction "R2_7") (pintype "passive"))
      (node (ref "U4") (pin "18") (pinfunction "PD12/LCD_D18_18") (pintype "passive"))
    )
    (net (code "26") (name "/LCD_D19") (class "Default")
      (node (ref "J2") (pin "8") (pinfunction "R3_8") (pintype "passive"))
      (node (ref "U4") (pin "19") (pinfunction "PD13/LCD_D19_19") (pintype "passive"))
    )
    (net (code "27") (name "/LCD_D20") (class "Default")
      (node (ref "J2") (pin "9") (pinfunction "R4_9") (pintype "passive"))
      (node (ref "U4") (pin "21") (pinfunction "PD14/LCD_D20_21") (pintype "passive"))
    )
    (net (code "28") (name "/LCD_D21") (class "Default")
      (node (ref "J2") (pin "10") (pinfunction "R5_10") (pintype "passive"))
      (node (ref "U4") (pin "23") (pinfunction "PD15/LCD_D21_23") (pintype "passive"))
    )
    (net (code "29") (name "/LCD_D22") (class "Default")
      (node (ref "J2") (pin "11") (pinfunction "R6_11") (pintype "passive"))
      (node (ref "U4") (pin "24") (pinfunction "PD16/LCD_D22_24") (pintype "passive"))
    )
    (net (code "30") (name "/LCD_D23") (class "Default")
      (node (ref "J2") (pin "12") (pinfunction "R7_12") (pintype "passive"))
      (node (ref "U4") (pin "25") (pinfunction "PD17/LCD_D23_25") (pintype "passive"))
    )
    (net (code "31") (name "/LCD_DE") (class "Default")
      (node (ref "J2") (pin "34") (pinfunction "DE_34") (pintype "passive"))
      (node (ref "U4") (pin "27") (pinfunction "PD19/LCD_DE_27") (pintype "passive"))
    )
    (net (code "32") (name "/LCD_HS") (class "Default")
      (node (ref "J2") (pin "32") (pinfunction "HSYNC_32") (pintype "passive"))
      (node (ref "U4") (pin "28") (pinfunction "PD20/LCD_HSYNC_28") (pintype "passive"))
    )
    (net (code "33") (name "/LCD_VS") (class "Default")
      (node (ref "J2") (pin "33") (pinfunction "VSYNC_33") (pintype "passive"))
      (node (ref "U4") (pin "29") (pinfunction "PD21/LCD_VSYNC_29") (pintype "passive"))
    )
    (net (code "34") (name "/LINL") (class "Default")
      (node (ref "U4") (pin "86") (pinfunction "LINL_86") (pintype "passive"))
    )
    (net (code "35") (name "/LRADC0") (class "Default")
      (node (ref "C42") (pin "1") (pintype "passive"))
      (node (ref "R23") (pin "2") (pinfunction "2_2") (pintype "passive"))
      (node (ref "R24") (pin "1") (pinfunction "1_1") (pintype "passive"))
      (node (ref "U4") (pin "79") (pinfunction "LRADC0_79") (pintype "passive"))
    )
    (net (code "36") (name "/MICIN") (class "Default")
      (node (ref "C43") (pin "1") (pinfunction "1_1") (pintype "passive"))
      (node (ref "U4") (pin "87") (pinfunction "MICIN_87") (pintype "passive"))
    )
    (net (code "37") (name "/MIC_CON") (class "Default")
      (node (ref "C43") (pin "2") (pinfunction "2_2") (pintype "passive"))
      (node (ref "C48") (pin "1") (pinfunction "1_1") (pintype "passive"))
      (node (ref "J3") (pin "2") (pinfunction "MIC_2") (pintype "passive"))
      (node (ref "MIC1") (pin "1") (pinfunction "+_1") (pintype "passive"))
      (node (ref "R32") (pin "1") (pinfunction "1_1") (pintype "passive"))
    )
    (net (code "38") (name "/PE2") (class "Default")
      (node (ref "R17") (pin "2") (pinfunction "2_2") (pintype "passive"))
      (node (ref "U4") (pin "47") (pinfunction "PE2_47") (pintype "passive"))
    )
    (net (code "39") (name "/PE4") (class "Default")
      (node (ref "P4") (pin "15") (pinfunction "15_15") (pintype "passive"))
      (node (ref "U4") (pin "45") (pinfunction "PE4_45") (pintype "passive"))
    )
    (net (code "40") (name "/PE5") (class "Default")
      (node (ref "P4") (pin "14") (pinfunction "14_14") (pintype "passive"))
      (node (ref "U4") (pin "44") (pinfunction "PE5_44") (pintype "passive"))
    )
    (net (code "41") (name "/PE7") (class "Default")
      (node (ref "P4") (pin "8") (pinfunction "8_8") (pintype "passive"))
      (node (ref "U4") (pin "42") (pinfunction "PE7_42") (pintype "passive"))
    )
    (net (code "42") (name "/PE8") (class "Default")
      (node (ref "P4") (pin "10") (pinfunction "10_10") (pintype "passive"))
      (node (ref "U4") (pin "41") (pinfunction "PE8_41") (pintype "passive"))
    )
    (net (code "43") (name "/PE9") (class "Default")
      (node (ref "P4") (pin "12") (pinfunction "12_12") (pintype "passive"))
      (node (ref "U4") (pin "40") (pinfunction "PE9_40") (pintype "passive"))
    )
    (net (code "44") (name "/PE10") (class "Default")
      (node (ref "P4") (pin "13") (pinfunction "13_13") (pintype "passive"))
      (node (ref "U4") (pin "39") (pinfunction "PE10_39") (pintype "passive"))
    )
    (net (code "46") (name "/PWM1") (class "Default")
      (node (ref "R6") (pin "1") (pinfunction "1_1") (pintype "passive"))
      (node (ref "U4") (pin "43") (pinfunction "PE6_43") (pintype "passive"))
    )
    (net (code "47") (name "/RESET") (class "Default")
      (node (ref "C10") (pin "1") (pintype "passive"))
      (node (ref "R9") (pin "2") (pinfunction "2_2") (pintype "passive"))
      (node (ref "S1") (pin "2") (pinfunction "2_2") (pintype "passive"))
      (node (ref "U4") (pin "70") (pinfunction "RESET_70") (pintype "passive"))
    )
    (net (code "48") (name "/SDIO_CLK") (class "Default")
      (node (ref "J1") (pin "5") (pinfunction "CLK_5") (pintype "passive"))
      (node (ref "U4") (pin "56") (pinfunction "PF2_56") (pintype "passive"))
    )
    (net (code "49") (name "/SDIO_CMD") (class "Default")
      (node (ref "J1") (pin "3") (pinfunction "CMD_3") (pintype "passive"))
      (node (ref "R3") (pin "2") (pinfunction "2_2") (pintype "passive"))
      (node (ref "U4") (pin "55") (pinfunction "PF3_55") (pintype "passive"))
    )
    (net (code "50") (name "/SDIO_D0") (class "Default")
      (node (ref "J1") (pin "7") (pinfunction "DAT0_7") (pintype "passive"))
      (node (ref "R2") (pin "2") (pinfunction "2_2") (pintype "passive"))
      (node (ref "U4") (pin "57") (pinfunction "PF1_57") (pintype "passive"))
    )
    (net (code "51") (name "/SDIO_D1") (class "Default")
      (node (ref "J1") (pin "8") (pinfunction "DAT1_8") (pintype "passive"))
      (node (ref "R1") (pin "2") (pinfunction "2_2") (pintype "passive"))
      (node (ref "U4") (pin "58") (pinfunction "PF0_58") (pintype "passive"))
    )
    (net (code "52") (name "/SDIO_D2") (class "Default")
      (node (ref "J1") (pin "1") (pinfunction "DAT2_1") (pintype "passive"))
      (node (ref "R5") (pin "2") (pinfunction "2_2") (pintype "passive"))
      (node (ref "U4") (pin "53") (pinfunction "PF5_53") (pintype "passive"))
    )
    (net (code "53") (name "/SDIO_D3") (class "Default")
      (node (ref "J1") (pin "2") (pinfunction "DAT3/CD_2") (pintype "passive"))
      (node (ref "R4") (pin "2") (pinfunction "2_2") (pintype "passive"))
      (node (ref "U4") (pin "54") (pinfunction "PF4_54") (pintype "passive"))
    )
    (net (code "54") (name "/SOC0") (class "Default")
      (node (ref "C26") (pin "1") (pintype "passive"))
      (node (ref "U4") (pin "52") (pinfunction "SOCO_52") (pintype "passive"))
      (node (ref "Y1") (pin "3") (pinfunction "3_3") (pintype "passive"))
    )
    (net (code "55") (name "/SOCI") (class "Default")
      (node (ref "C25") (pin "1") (pintype "passive"))
      (node (ref "U4") (pin "51") (pinfunction "SOCI_51") (pintype "passive"))
      (node (ref "Y1") (pin "1") (pinfunction "1_1") (pintype "passive"))
    )
    (net (code "56") (name "/SPI0_CLK") (class "Default")
      (node (ref "U4") (pin "59") (pinfunction "PC0_59") (pintype "passive"))
      (node (ref "U8") (pin "6") (pinfunction "CLK_6") (pintype "passive"))
    )
    (net (code "57") (name "/SPI0_CS") (class "Default")
      (node (ref "R37") (pin "2") (pinfunction "2_2") (pintype "passive"))
      (node (ref "U4") (pin "60") (pinfunction "PC1_60") (pintype "passive"))
      (node (ref "U8") (pin "1") (pinfunction "CS#_1") (pintype "passive"))
    )
    (net (code "58") (name "/SPI0_MISO") (class "Default")
      (node (ref "U4") (pin "61") (pinfunction "PC2_61") (pintype "passive"))
      (node (ref "U8") (pin "2") (pinfunction "MISO_2") (pintype "passive"))
    )
    (net (code "59") (name "/SPI0_MOSI") (class "Default")
      (node (ref "U4") (pin "62") (pinfunction "PC3_62") (pintype "passive"))
      (node (ref "U8") (pin "5") (pinfunction "MOSI_5") (pintype "passive"))
    )
    (net (code "60") (name "/SPI1_CLK") (class "Default")
      (node (ref "P4") (pin "5") (pinfunction "5_5") (pintype "passive"))
      (node (ref "U4") (pin "64") (pinfunction "PA2_64") (pintype "passive"))
    )
    (net (code "61") (name "/SPI1_CS") (class "Default")
      (node (ref "P4") (pin "9") (pinfunction "9_9") (pintype "passive"))
      (node (ref "U4") (pin "66") (pinfunction "PA0_66") (pintype "passive"))
    )
    (net (code "62") (name "/SPI1_MISO") (class "Default")
      (node (ref "P4") (pin "3") (pinfunction "3_3") (pintype "passive"))
      (node (ref "U4") (pin "63") (pinfunction "PA3_63") (pintype "passive"))
    )
    (net (code "63") (name "/SPI1_MOSI") (class "Default")
      (node (ref "P4") (pin "7") (pinfunction "7_7") (pintype "passive"))
      (node (ref "U4") (pin "65") (pinfunction "PA1_65") (pintype "passive"))
    )
    (net (code "64") (name "/TV_IN0") (class "Default")
      (node (ref "U4") (pin "78") (pinfunction "TV_IN0_78") (pintype "passive"))
    )
    (net (code "65") (name "/TV_IN1") (class "Default")
      (node (ref "U4") (pin "77") (pinfunction "TV_IN1_77") (pintype "passive"))
    )
    (net (code "66") (name "/TV_OUT") (class "Default")
      (node (ref "U4") (pin "72") (pinfunction "TV_OUT_72") (pintype "passive"))
    )
    (net (code "67") (name "/TV_VRN") (class "Default")
      (node (ref "U4") (pin "75") (pinfunction "TV_VRN_75") (pintype "passive"))
    )
    (net (code "68") (name "/TV_VRP") (class "Default")
      (node (ref "U4") (pin "76") (pinfunction "TV_VRP_76") (pintype "passive"))
    )
    (net (code "69") (name "/TWI0_SCK") (class "Default")
      (node (ref "P3") (pin "1") (pinfunction "1_1") (pintype "passive"))
      (node (ref "P4") (pin "18") (pinfunction "18_18") (pintype "passive"))
      (node (ref "R15") (pin "1") (pinfunction "1_1") (pintype "passive"))
      (node (ref "U4") (pin "38") (pinfunction "PE11_38") (pintype "passive"))
    )
    (net (code "70") (name "/TWI0_SDA") (class "Default")
      (node (ref "P3") (pin "2") (pinfunction "2_2") (pintype "passive"))
      (node (ref "P4") (pin "16") (pinfunction "16_16") (pintype "passive"))
      (node (ref "R14") (pin "1") (pinfunction "1_1") (pintype "passive"))
      (node (ref "U4") (pin "37") (pinfunction "PE12/DA_MCLK/TWIO_SDA/PWM0_37") (pintype "passive"))
    )
    (net (code "71") (name "/USART0_RX") (class "Default")
      (node (ref "U4") (pin "49") (pinfunction "PE0_49") (pintype "passive"))
      (node (ref "U5") (pin "21") (pinfunction "TXD_21") (pintype "passive"))
    )
    (net (code "72") (name "/USART0_TX") (class "Default")
      (node (ref "U4") (pin "48") (pinfunction "PE1_48") (pintype "passive"))
      (node (ref "U5") (pin "20") (pinfunction "RXD_20") (pintype "passive"))
    )
    (net (code "77") (name "/USB_ID") (class "Default")
      (node (ref "*2") (pin "4") (pinfunction "ID_4") (pintype "passive"))
      (node (ref "R17") (pin "1") (pinfunction "1_1") (pintype "passive"))
      (node (ref "R18") (pin "1") (pinfunction "1_1") (pintype "passive"))
    )
    (net (code "78") (name "/VLED+") (class "Default")
      (node (ref "C3") (pin "2") (pinfunction "2_2") (pintype "passive"))
      (node (ref "C4") (pin "2") (pinfunction "2_2") (pintype "passive"))
      (node (ref "D1") (pin "2") (pinfunction "2_2") (pintype "passive"))
      (node (ref "J2") (pin "2") (pinfunction "VLED+_2") (pintype "passive"))
      (node (ref "U2") (pin "5") (pinfunction "OVR_5") (pintype "passive"))
    )
    (net (code "79") (name "/VLED-") (class "Default")
      (node (ref "J2") (pin "1") (pinfunction "VLED-_1") (pintype "passive"))
      (node (ref "R7") (pin "1") (pinfunction "1_1") (pintype "passive"))
      (node (ref "U2") (pin "3") (pinfunction "FB_3") (pintype "passive"))
    )
    (net (code "80") (name "/VRA1") (class "Default")
      (node (ref "C9") (pin "1") (pintype "passive"))
      (node (ref "U4") (pin "81") (pinfunction "VRA1_81") (pintype "passive"))
    )
    (net (code "81") (name "/VRA2") (class "Default")
      (node (ref "C7") (pin "2") (pintype "passive"))
      (node (ref "C8") (pin "2") (pintype "passive"))
      (node (ref "R8") (pin "1") (pinfunction "1_1") (pintype "passive"))
      (node (ref "U4") (pin "83") (pinfunction "VRA2_83") (pintype "passive"))
    )
    (net (code "82") (name "GND") (class "Default")
      (node (ref "*1") (pin "5") (pinfunction "GND_5") (pintype "passive"))
      (node (ref "*2") (pin "5") (pinfunction "GND_5") (pintype "passive"))
      (node (ref "C1") (pin "1") (pinfunction "1_1") (pintype "passive"))
      (node (ref "C10") (pin "2") (pintype "passive"))
      (node (ref "C11") (pin "1") (pinfunction "1_1") (pintype "passive"))
      (node (ref "C12") (pin "1") (pinfunction "1_1") (pintype "passive"))
      (node (ref "C13") (pin "1") (pinfunction "1_1") (pintype "passive"))
      (node (ref "C14") (pin "1") (pinfunction "1_1") (pintype "passive"))
      (node (ref "C15") (pin "1") (pintype "passive"))
      (node (ref "C16") (pin "1") (pintype "passive"))
      (node (ref "C17") (pin "2") (pinfunction "2_2") (pintype "passive"))
      (node (ref "C18") (pin "2") (pintype "passive"))
      (node (ref "C19") (pin "2") (pintype "passive"))
      (node (ref "C2") (pin "1") (pinfunction "1_1") (pintype "passive"))
      (node (ref "C20") (pin "2") (pintype "passive"))
      (node (ref "C21") (pin "1") (pintype "passive"))
      (node (ref "C22") (pin "2") (pintype "passive"))
      (node (ref "C23") (pin "2") (pintype "passive"))
      (node (ref "C24") (pin "2") (pintype "passive"))
      (node (ref "C25") (pin "2") (pintype "passive"))
      (node (ref "C26") (pin "2") (pintype "passive"))
      (node (ref "C27") (pin "2") (pintype "passive"))
      (node (ref "C28") (pin "2") (pintype "passive"))
      (node (ref "C29") (pin "2") (pintype "passive"))
      (node (ref "C3") (pin "1") (pinfunction "1_1") (pintype "passive"))
      (node (ref "C30") (pin "2") (pintype "passive"))
      (node (ref "C32") (pin "1") (pintype "passive"))
      (node (ref "C33") (pin "1") (pinfunction "1_1") (pintype "passive"))
      (node (ref "C35") (pin "1") (pinfunction "1_1") (pintype "passive"))
      (node (ref "C38") (pin "2") (pintype "passive"))
      (node (ref "C39") (pin "2") (pintype "passive"))
      (node (ref "C4") (pin "1") (pinfunction "1_1") (pintype "passive"))
      (node (ref "C40") (pin "2") (pintype "passive"))
      (node (ref "C41") (pin "2") (pintype "passive"))
      (node (ref "C42") (pin "2") (pintype "passive"))
      (node (ref "C44") (pin "2") (pintype "passive"))
      (node (ref "C45") (pin "2") (pintype "passive"))
      (node (ref "C46") (pin "2") (pinfunction "2_2") (pintype "passive"))
      (node (ref "C47") (pin "2") (pinfunction "2_2") (pintype "passive"))
      (node (ref "C48") (pin "2") (pinfunction "2_2") (pintype "passive"))
      (node (ref "C49") (pin "2") (pintype "passive"))
      (node (ref "C50") (pin "2") (pintype "passive"))
      (node (ref "C51") (pin "2") (pintype "passive"))
      (node (ref "C52") (pin "2") (pintype "passive"))
      (node (ref "C53") (pin "1") (pinfunction "1_1") (pintype "passive"))
      (node (ref "C6") (pin "2") (pintype "passive"))
      (node (ref "C7") (pin "1") (pintype "passive"))
      (node (ref "C8") (pin "1") (pintype "passive"))
      (node (ref "C9") (pin "2") (pintype "passive"))
      (node (ref "D3") (pin "2") (pinfunction "2_2") (pintype "passive"))
      (node (ref "D4") (pin "2") (pinfunction "2_2") (pintype "passive"))
      (node (ref "D5") (pin "1") (pinfunction "1_1") (pintype "passive"))
      (node (ref "D6") (pin "1") (pinfunction "1_1") (pintype "passive"))
      (node (ref "J1") (pin "10") (pinfunction "SHIELD_10") (pintype "passive"))
      (node (ref "J1") (pin "6") (pinfunction "VSS_6") (pintype "passive"))
      (node (ref "J2") (pin "13") (pinfunction "G0_13") (pintype "passive"))
      (node (ref "J2") (pin "14") (pinfunction "G1_14") (pintype "passive"))
      (node (ref "J2") (pin "21") (pinfunction "B0_21") (pintype "passive"))
      (node (ref "J2") (pin "22") (pinfunction "B1_22") (pintype "passive"))
      (node (ref "J2") (pin "29") (pinfunction "GND2_29") (pintype "passive"))
      (node (ref "J2") (pin "3") (pinfunction "GND1_3") (pintype "passive"))
      (node (ref "J2") (pin "36") (pinfunction "GND3_36") (pintype "passive"))
      (node (ref "J2") (pin "41") (pinfunction "GNDB_41") (pintype "passive"))
      (node (ref "J2") (pin "42") (pinfunction "GNDA_42") (pintype "passive"))
      (node (ref "J2") (pin "5") (pinfunction "R0_5") (pintype "passive"))
      (node (ref "J2") (pin "6") (pinfunction "R1_6") (pintype "passive"))
      (node (ref "MIC1") (pin "2") (pinfunction "-_2") (pintype "passive"))
      (node (ref "P3") (pin "4") (pinfunction "4_4") (pintype "passive"))
      (node (ref "P4") (pin "11") (pinfunction "11_11") (pintype "passive"))
      (node (ref "P4") (pin "19") (pinfunction "19_19") (pintype "passive"))
      (node (ref "P4") (pin "20") (pinfunction "20_20") (pintype "passive"))
      (node (ref "P4") (pin "4") (pinfunction "4_4") (pintype "passive"))
      (node (ref "R20") (pin "1") (pinfunction "1_1") (pintype "passive"))
      (node (ref "R22") (pin "1") (pinfunction "1_1") (pintype "passive"))
      (node (ref "R29") (pin "2") (pinfunction "2_2") (pintype "passive"))
      (node (ref "R30") (pin "1") (pinfunction "1_1") (pintype "passive"))
      (node (ref "R34") (pin "1") (pinfunction "1_1") (pintype "passive"))
      (node (ref "R36") (pin "1") (pinfunction "1_1") (pintype "passive"))
      (node (ref "R7") (pin "2") (pinfunction "2_2") (pintype "passive"))
      (node (ref "R8") (pin "2") (pinfunction "2_2") (pintype "passive"))
      (node (ref "S1") (pin "1") (pinfunction "1_1") (pintype "passive"))
      (node (ref "SW1") (pin "1") (pinfunction "1_1") (pintype "passive"))
      (node (ref "SW2") (pin "1") (pinfunction "1_1") (pintype "passive"))
      (node (ref "SW3") (pin "1") (pinfunction "1_1") (pintype "passive"))
      (node (ref "SW4") (pin "1") (pinfunction "1_1") (pintype "passive"))
      (node (ref "U2") (pin "2") (pinfunction "GND_2") (pintype "passive"))
      (node (ref "U3") (pin "11") (pinfunction "GND_11") (pintype "passive"))
      (node (ref "U3") (pin "2") (pinfunction "PGND_2") (pintype "passive"))
      (node (ref "U3") (pin "9") (pinfunction "GND_9") (pintype "passive"))
      (node (ref "U4") (pin "74") (pinfunction "TV_GND_74") (pintype "passive"))
      (node (ref "U4") (pin "82") (pinfunction "AGND_82") (pintype "passive"))
      (node (ref "U4") (pin "89") (pinfunction "EPAD_89") (pintype "passive"))
      (node (ref "U5") (pin "2") (pinfunction "GND_2") (pintype "passive"))
      (node (ref "U5") (pin "25") (pinfunction "PAD_25") (pintype "passive"))
      (node (ref "U6") (pin "1") (pinfunction "GND_1") (pintype "passive"))
      (node (ref "U7") (pin "1") (pinfunction "GND_1") (pintype "passive"))
      (node (ref "U7") (pin "12") (pinfunction "GND_12") (pintype "passive"))
      (node (ref "U7") (pin "13") (pinfunction "AGND_13") (pintype "passive"))
      (node (ref "U7") (pin "15") (pinfunction "AGND_15") (pintype "passive"))
      (node (ref "U7") (pin "17") (pinfunction "AGND_17") (pintype "passive"))
      (node (ref "U7") (pin "21") (pinfunction "PAD_21") (pintype "passive"))
      (node (ref "U7") (pin "4") (pinfunction "AGND_4") (pintype "passive"))
      (node (ref "U7") (pin "5") (pinfunction "GND_5") (pintype "passive"))
      (node (ref "U8") (pin "4") (pinfunction "VSS_4") (pintype "passive"))
      (node (ref "Y1") (pin "2") (pinfunction "2_2") (pintype "passive"))
      (node (ref "Y1") (pin "4") (pinfunction "4_4") (pintype "passive"))
    )
    (net (code "83") (name "Net-(*1-D+)") (class "Default")
      (node (ref "*1") (pin "3") (pinfunction "D+_3") (pintype "passive"))
      (node (ref "D6") (pin "2") (pinfunction "2_2") (pintype "passive"))
      (node (ref "U5") (pin "3") (pinfunction "D+_3") (pintype "passive"))
    )
    (net (code "84") (name "Net-(*1-D-)") (class "Default")
      (node (ref "*1") (pin "2") (pinfunction "D-_2") (pintype "passive"))
      (node (ref "D5") (pin "2") (pinfunction "2_2") (pintype "passive"))
      (node (ref "U5") (pin "4") (pinfunction "D-_4") (pintype "passive"))
    )
    (net (code "85") (name "Net-(C37-Pad1)") (class "Default")
      (node (ref "C37") (pin "1") (pinfunction "1_1") (pintype "passive"))
      (node (ref "R22") (pin "2") (pinfunction "2_2") (pintype "passive"))
    )
    (net (code "86") (name "Net-(C47-Pad1)") (class "Default")
      (node (ref "C47") (pin "1") (pinfunction "1_1") (pintype "passive"))
      (node (ref "R31") (pin "1") (pinfunction "1_1") (pintype "passive"))
      (node (ref "R32") (pin "2") (pinfunction "2_2") (pintype "passive"))
    )
    (net (code "87") (name "Net-(D2-K)") (class "Default")
      (node (ref "D2") (pin "2") (pinfunction "K_2") (pintype "passive"))
      (node (ref "R29") (pin "1") (pinfunction "1_1") (pintype "passive"))
    )
    (net (code "88") (name "Net-(J3-L)") (class "Default")
      (node (ref "C36") (pin "2") (pinfunction "2_2") (pintype "passive"))
      (node (ref "J3") (pin "6") (pinfunction "L_6") (pintype "passive"))
    )
    (net (code "89") (name "Net-(J3-R)") (class "Default")
      (node (ref "C34") (pin "2") (pinfunction "2_2") (pintype "passive"))
      (node (ref "J3") (pin "4") (pinfunction "R_4") (pintype "passive"))
    )
    (net (code "90") (name "Net-(P3-Pad6)") (class "Default")
      (node (ref "P3") (pin "6") (pinfunction "6_6") (pintype "passive"))
      (node (ref "R16") (pin "1") (pinfunction "1_1") (pintype "passive"))
    )
    (net (code "91") (name "Net-(R24-Pad2)") (class "Default")
      (node (ref "R24") (pin "2") (pinfunction "2_2") (pintype "passive"))
      (node (ref "R25") (pin "1") (pinfunction "1_1") (pintype "passive"))
      (node (ref "SW1") (pin "2") (pinfunction "2_2") (pintype "passive"))
    )
    (net (code "92") (name "Net-(R25-Pad2)") (class "Default")
      (node (ref "R25") (pin "2") (pinfunction "2_2") (pintype "passive"))
      (node (ref "R26") (pin "1") (pinfunction "1_1") (pintype "passive"))
      (node (ref "SW2") (pin "2") (pinfunction "2_2") (pintype "passive"))
    )
    (net (code "93") (name "Net-(R26-Pad2)") (class "Default")
      (node (ref "R26") (pin "2") (pinfunction "2_2") (pintype "passive"))
      (node (ref "R27") (pin "1") (pinfunction "1_1") (pintype "passive"))
      (node (ref "SW3") (pin "2") (pinfunction "2_2") (pintype "passive"))
    )
    (net (code "94") (name "Net-(R27-Pad2)") (class "Default")
      (node (ref "R27") (pin "2") (pinfunction "2_2") (pintype "passive"))
      (node (ref "SW4") (pin "2") (pinfunction "2_2") (pintype "passive"))
    )
    (net (code "95") (name "Net-(U2-EN)") (class "Default")
      (node (ref "R6") (pin "2") (pinfunction "2_2") (pintype "passive"))
      (node (ref "U2") (pin "4") (pinfunction "EN_4") (pintype "passive"))
    )
    (net (code "96") (name "Net-(U2-LX)") (class "Default")
      (node (ref "D1") (pin "1") (pinfunction "1_1") (pintype "passive"))
      (node (ref "L1") (pin "2") (pinfunction "2_2") (pintype "passive"))
      (node (ref "U2") (pin "1") (pinfunction "LX_1") (pintype "passive"))
    )
    (net (code "97") (name "Net-(U3-+OUT_L)") (class "Default")
      (node (ref "P1") (pin "1") (pinfunction "1_1") (pintype "passive"))
      (node (ref "U3") (pin "3") (pinfunction "+OUT_L_3") (pintype "passive"))
    )
    (net (code "98") (name "Net-(U3-+OUT_R)") (class "Default")
      (node (ref "P2") (pin "2") (pinfunction "2_2") (pintype "passive"))
      (node (ref "U3") (pin "14") (pinfunction "+OUT_R_14") (pintype "passive"))
    )
    (net (code "99") (name "Net-(U3--OUT_L)") (class "Default")
      (node (ref "P1") (pin "2") (pinfunction "2_2") (pintype "passive"))
      (node (ref "U3") (pin "1") (pinfunction "-OUT_L_1") (pintype "passive"))
    )
    (net (code "100") (name "Net-(U3--OUT_R)") (class "Default")
      (node (ref "P2") (pin "1") (pinfunction "1_1") (pintype "passive"))
      (node (ref "U3") (pin "16") (pinfunction "-OUT_R_16") (pintype "passive"))
    )
    (net (code "101") (name "Net-(U3-INL)") (class "Default")
      (node (ref "R11") (pin "1") (pinfunction "1_1") (pintype "passive"))
      (node (ref "U3") (pin "7") (pinfunction "INL_7") (pintype "passive"))
    )
    (net (code "102") (name "Net-(U3-INR)") (class "Default")
      (node (ref "R12") (pin "1") (pinfunction "1_1") (pintype "passive"))
      (node (ref "U3") (pin "10") (pinfunction "INR_10") (pintype "passive"))
    )
    (net (code "103") (name "Net-(U3-SHDN)") (class "Default")
      (node (ref "R10") (pin "1") (pinfunction "1_1") (pintype "passive"))
      (node (ref "U3") (pin "12") (pinfunction "SHDN_12") (pintype "passive"))
    )
    (net (code "104") (name "Net-(U3-VDD)") (class "Default")
      (node (ref "L2") (pin "1") (pinfunction "1_1") (pintype "passive"))
      (node (ref "U3") (pin "6") (pinfunction "VDD_6") (pintype "passive"))
    )
    (net (code "105") (name "Net-(U3-VREF)") (class "Default")
      (node (ref "C17") (pin "1") (pinfunction "1_1") (pintype "passive"))
      (node (ref "U3") (pin "8") (pinfunction "VREF_8") (pintype "passive"))
    )
    (net (code "106") (name "Net-(U4-SVREF)") (class "Default")
      (node (ref "C31") (pin "1") (pintype "passive"))
      (node (ref "C32") (pin "2") (pintype "passive"))
      (node (ref "R19") (pin "1") (pinfunction "1_1") (pintype "passive"))
      (node (ref "R20") (pin "2") (pinfunction "2_2") (pintype "passive"))
      (node (ref "U4") (pin "33") (pinfunction "SVREF_33") (pintype "passive"))
    )
    (net (code "107") (name "Net-(U5-RST)") (class "Default")
      (node (ref "R13") (pin "1") (pinfunction "1_1") (pintype "passive"))
      (node (ref "U5") (pin "9") (pinfunction "RST_9") (pintype "passive"))
    )
    (net (code "108") (name "Net-(U7-FB1)") (class "Default")
      (node (ref "R28") (pin "1") (pinfunction "1_1") (pintype "passive"))
      (node (ref "R30") (pin "2") (pinfunction "2_2") (pintype "passive"))
      (node (ref "U7") (pin "14") (pinfunction "FB1_14") (pintype "passive"))
    )
    (net (code "109") (name "Net-(U7-FB2)") (class "Default")
      (node (ref "R33") (pin "1") (pinfunction "1_1") (pintype "passive"))
      (node (ref "R34") (pin "2") (pinfunction "2_2") (pintype "passive"))
      (node (ref "U7") (pin "3") (pinfunction "FB2_3") (pintype "passive"))
    )
    (net (code "110") (name "Net-(U7-FB3)") (class "Default")
      (node (ref "R35") (pin "1") (pinfunction "1_1") (pintype "passive"))
      (node (ref "R36") (pin "2") (pinfunction "2_2") (pintype "passive"))
      (node (ref "U7") (pin "2") (pinfunction "FB3_2") (pintype "passive"))
    )
    (net (code "111") (name "Net-(U7-SW1)") (class "Default")
      (node (ref "L3") (pin "2") (pinfunction "2_2") (pintype "passive"))
      (node (ref "U7") (pin "11") (pinfunction "SW1_11") (pintype "passive"))
    )
    (net (code "112") (name "Net-(U7-SW2)") (class "Default")
      (node (ref "L4") (pin "2") (pinfunction "2_2") (pintype "passive"))
      (node (ref "U7") (pin "6") (pinfunction "SW2_6") (pintype "passive"))
    )
    (net (code "113") (name "Net-(U7-SW3)") (class "Default")
      (node (ref "L5") (pin "2") (pinfunction "2_2") (pintype "passive"))
      (node (ref "U7") (pin "20") (pinfunction "SW3_20") (pintype "passive"))
    )
    (net (code "114") (name "Net-(U8-HOLD#)") (class "Default")
      (node (ref "R38") (pin "2") (pinfunction "2_2") (pintype "passive"))
      (node (ref "U8") (pin "7") (pinfunction "HOLD#_7") (pintype "passive"))
    )
    (net (code "115") (name "USB_D+") (class "Default")
      (node (ref "*2") (pin "3") (pinfunction "D+_3") (pintype "passive"))
      (node (ref "D4") (pin "1") (pinfunction "1_1") (pintype "passive"))
      (node (ref "U4") (pin "69") (pinfunction "USB+DP_69") (pintype "passive"))
    )
    (net (code "116") (name "USB_D-") (class "Default")
      (node (ref "*2") (pin "2") (pinfunction "D-_2") (pintype "passive"))
      (node (ref "D3") (pin "1") (pinfunction "1_1") (pintype "passive"))
      (node (ref "U4") (pin "68") (pinfunction "USB_DM_68") (pintype "passive"))
    )
    (net (code "117") (name "VCC") (class "Default")
      (node (ref "*1") (pin "1") (pinfunction "VUSB_1") (pintype "passive"))
      (node (ref "*2") (pin "1") (pinfunction "VUSB_1") (pintype "passive"))
      (node (ref "C1") (pin "2") (pinfunction "2_2") (pintype "passive"))
      (node (ref "C11") (pin "2") (pinfunction "2_2") (pintype "passive"))
      (node (ref "C12") (pin "2") (pinfunction "2_2") (pintype "passive"))
      (node (ref "C13") (pin "2") (pinfunction "2_2") (pintype "passive"))
      (node (ref "C14") (pin "2") (pinfunction "2_2") (pintype "passive"))
      (node (ref "C18") (pin "1") (pintype "passive"))
      (node (ref "C2") (pin "2") (pinfunction "2_2") (pintype "passive"))
      (node (ref "C38") (pin "1") (pintype "passive"))
      (node (ref "C39") (pin "1") (pintype "passive"))
      (node (ref "L1") (pin "1") (pinfunction "1_1") (pintype "passive"))
      (node (ref "L2") (pin "2") (pinfunction "2_2") (pintype "passive"))
      (node (ref "P4") (pin "2") (pinfunction "2_2") (pintype "passive"))
      (node (ref "R10") (pin "2") (pinfunction "2_2") (pintype "passive"))
      (node (ref "U2") (pin "6") (pinfunction "VDD_6") (pintype "passive"))
      (node (ref "U3") (pin "13") (pinfunction "PVDD_13") (pintype "passive"))
      (node (ref "U3") (pin "4") (pinfunction "PVDD_4") (pintype "passive"))
      (node (ref "U3") (pin "5") (pinfunction "MUTE_5") (pintype "passive"))
      (node (ref "U5") (pin "7") (pinfunction "REGIN_7") (pintype "passive"))
      (node (ref "U5") (pin "8") (pinfunction "VBUS_8") (pintype "passive"))
      (node (ref "U7") (pin "10") (pinfunction "VIN1_10") (pintype "passive"))
      (node (ref "U7") (pin "16") (pinfunction "VCC_16") (pintype "passive"))
      (node (ref "U7") (pin "18") (pinfunction "EN3_18") (pintype "passive"))
      (node (ref "U7") (pin "19") (pinfunction "VIN3_19") (pintype "passive"))
      (node (ref "U7") (pin "7") (pinfunction "VIN2_7") (pintype "passive"))
      (node (ref "U7") (pin "8") (pinfunction "EN2_8") (pintype "passive"))
      (node (ref "U7") (pin "9") (pinfunction "EN1_9") (pintype "passive"))
    )
    (net (code "118") (name "VDDA") (class "Default")
      (node (ref "C46") (pin "1") (pinfunction "1_1") (pintype "passive"))
      (node (ref "C51") (pin "1") (pintype "passive"))
      (node (ref "C52") (pin "1") (pintype "passive"))
      (node (ref "R23") (pin "1") (pinfunction "1_1") (pintype "passive"))
      (node (ref "R31") (pin "2") (pinfunction "2_2") (pintype "passive"))
      (node (ref "U4") (pin "80") (pinfunction "AVCC_80") (pintype "passive"))
      (node (ref "U6") (pin "2") (pinfunction "VO_2") (pintype "passive"))
    )
    (net (code "119") (name "unconnected-(*1-ID-Pad4)") (class "Default")
      (node (ref "*1") (pin "4") (pinfunction "ID_4") (pintype "passive"))
    )
    (net (code "120") (name "unconnected-(*1-NOP-Pad6)") (class "Default")
      (node (ref "*1") (pin "6") (pinfunction "NOP_6") (pintype "passive"))
    )
    (net (code "121") (name "unconnected-(*1-NOP-Pad7)") (class "Default")
      (node (ref "*1") (pin "7") (pinfunction "NOP_7") (pintype "passive"))
    )
    (net (code "122") (name "unconnected-(*2-NOP-Pad6)") (class "Default")
      (node (ref "*2") (pin "6") (pinfunction "NOP_6") (pintype "passive"))
    )
    (net (code "123") (name "unconnected-(*2-NOP-Pad7)") (class "Default")
      (node (ref "*2") (pin "7") (pinfunction "NOP_7") (pintype "passive"))
    )
    (net (code "124") (name "unconnected-(J1-DET-Pad9)") (class "Default")
      (node (ref "J1") (pin "9") (pinfunction "DET_9") (pintype "passive+no_connect"))
    )
    (net (code "125") (name "unconnected-(J2-NC2-Pad37)") (class "Default")
      (node (ref "J2") (pin "37") (pinfunction "NC2_37") (pintype "passive"))
    )
    (net (code "126") (name "unconnected-(J2-NC3-Pad38)") (class "Default")
      (node (ref "J2") (pin "38") (pinfunction "NC3_38") (pintype "passive"))
    )
    (net (code "127") (name "unconnected-(J2-NC4-Pad39)") (class "Default")
      (node (ref "J2") (pin "39") (pinfunction "NC4_39") (pintype "passive"))
    )
    (net (code "128") (name "unconnected-(J2-NC5-Pad40)") (class "Default")
      (node (ref "J2") (pin "40") (pinfunction "NC5_40") (pintype "passive"))
    )
    (net (code "129") (name "unconnected-(J3-L_DET-Pad7)") (class "Default")
      (node (ref "J3") (pin "7") (pinfunction "L_DET_7") (pintype "passive"))
    )
    (net (code "130") (name "unconnected-(J3-R_DET-Pad5)") (class "Default")
      (node (ref "J3") (pin "5") (pinfunction "R_DET_5") (pintype "passive"))
    )
    (net (code "131") (name "unconnected-(U3-PGND-Pad15)") (class "Default")
      (node (ref "U3") (pin "15") (pinfunction "PGND_15") (pintype "passive"))
    )
    (net (code "132") (name "unconnected-(U5-CTS-Pad18)") (class "Default")
      (node (ref "U5") (pin "18") (pinfunction "CTS_18") (pintype "passive+no_connect"))
    )
    (net (code "133") (name "unconnected-(U5-DCD-Pad24)") (class "Default")
      (node (ref "U5") (pin "24") (pinfunction "DCD_24") (pintype "passive+no_connect"))
    )
    (net (code "134") (name "unconnected-(U5-DSR-Pad22)") (class "Default")
      (node (ref "U5") (pin "22") (pinfunction "DSR_22") (pintype "passive+no_connect"))
    )
    (net (code "135") (name "unconnected-(U5-DTR-Pad23)") (class "Default")
      (node (ref "U5") (pin "23") (pinfunction "DTR_23") (pintype "passive+no_connect"))
    )
    (net (code "136") (name "unconnected-(U5-GPIO.0-Pad14)") (class "Default")
      (node (ref "U5") (pin "14") (pinfunction "GPIO.0_14") (pintype "passive+no_connect"))
    )
    (net (code "137") (name "unconnected-(U5-GPIO.1-Pad13)") (class "Default")
      (node (ref "U5") (pin "13") (pinfunction "GPIO.1_13") (pintype "passive+no_connect"))
    )
    (net (code "138") (name "unconnected-(U5-GPIO.2-Pad12)") (class "Default")
      (node (ref "U5") (pin "12") (pinfunction "GPIO.2_12") (pintype "passive+no_connect"))
    )
    (net (code "139") (name "unconnected-(U5-GPIO.3-Pad11)") (class "Default")
      (node (ref "U5") (pin "11") (pinfunction "GPIO.3_11") (pintype "passive+no_connect"))
    )
    (net (code "140") (name "unconnected-(U5-RI-Pad1)") (class "Default")
      (node (ref "U5") (pin "1") (pinfunction "RI_1") (pintype "passive+no_connect"))
    )
    (net (code "141") (name "unconnected-(U5-RTS-Pad19)") (class "Default")
      (node (ref "U5") (pin "19") (pinfunction "RTS_19") (pintype "passive+no_connect"))
    )
    (net (code "142") (name "unconnected-(U5-SUSPEND-Pad15)") (class "Default")
      (node (ref "U5") (pin "15") (pinfunction "SUSPEND_15") (pintype "passive+no_connect"))
    )
    (net (code "143") (name "unconnected-(U5-SUSPEND-Pad17)") (class "Default")
      (node (ref "U5") (pin "17") (pinfunction "SUSPEND_17") (pintype "passive+no_connect"))
    )
    (net (code "144") (name "unconnected-(U5-VIO{slash}NC-Pad10)") (class "Default")
      (node (ref "U5") (pin "10") (pinfunction "VIO/NC_10") (pintype "passive+no_connect"))
    )
    (net (code "145") (name "unconnected-(U5-VPP-Pad16)") (class "Default")
      (node (ref "U5") (pin "16") (pinfunction "VPP_16") (pintype "passive+no_connect"))
    )
  )
)
